# Sumo_sensors.net
KiCad netlist of a schematic drawn in EAGLE
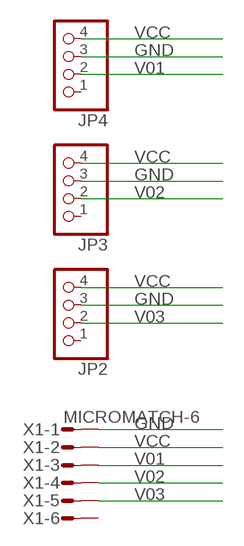
[diagram p0: schematic, sheet 1]

(export (version "E")
  (design (tool "Eeschema 10.0.6"))
  (components
    (comp (ref "JP2")
      (value "PINHD-1X4")
      (footprint "eagle-import:1X04")
      (libsource (lib "eagle-import") (part "PINHD-1X4"))
    )
    (comp (ref "JP3")
      (value "PINHD-1X4")
      (footprint "eagle-import:1X04")
      (libsource (lib "eagle-import") (part "PINHD-1X4"))
    )
    (comp (ref "JP4")
      (value "PINHD-1X4")
      (footprint "eagle-import:1X04")
      (libsource (lib "eagle-import") (part "PINHD-1X4"))
    )
    (comp (ref "X1")
      (value "MICROMATCH-6")
      (footprint "eagle-import:MICROMATCH-6")
      (fields (field (name "MPN") "7-215464-6"))
      (libsource (lib "eagle-import") (part "MICROMATCH-6"))
    )
  )
  (nets
    (net (code "1") (name "/GND") (class "Default")
      (node (ref "JP2") (pin "3") (pinfunction "3_3") (pintype "passive"))
      (node (ref "JP3") (pin "3") (pinfunction "3_3") (pintype "passive"))
      (node (ref "JP4") (pin "3") (pinfunction "3_3") (pintype "passive"))
      (node (ref "X1") (pin "1") (pinfunction "S_1") (pintype "passive"))
    )
    (net (code "2") (name "/V01") (class "Default")
      (node (ref "JP4") (pin "2") (pinfunction "2_2") (pintype "passive"))
      (node (ref "X1") (pin "3") (pinfunction "S_3") (pintype "passive"))
    )
    (net (code "3") (name "/V02") (class "Default")
      (node (ref "JP3") (pin "2") (pinfunction "2_2") (pintype "passive"))
      (node (ref "X1") (pin "4") (pinfunction "S_4") (pintype "passive"))
    )
    (net (code "4") (name "/V03") (class "Default")
      (node (ref "JP2") (pin "2") (pinfunction "2_2") (pintype "passive"))
      (node (ref "X1") (pin "5") (pinfunction "S_5") (pintype "passive"))
    )
    (net (code "5") (name "/VCC") (class "Default")
      (node (ref "JP2") (pin "4") (pinfunction "4_4") (pintype "passive"))
      (node (ref "JP3") (pin "4") (pinfunction "4_4") (pintype "passive"))
      (node (ref "JP4") (pin "4") (pinfunction "4_4") (pintype "passive"))
      (node (ref "X1") (pin "2") (pinfunction "S_2") (pintype "passive"))
    )
    (net (code "6") (name "unconnected-(JP2-Pad1)") (class "Default")
      (node (ref "JP2") (pin "1") (pinfunction "1_1") (pintype "passive"))
    )
    (net (code "7") (name "unconnected-(JP3-Pad1)") (class "Default")
      (node (ref "JP3") (pin "1") (pinfunction "1_1") (pintype "passive"))
    )
    (net (code "8") (name "unconnected-(JP4-Pad1)") (class "Default")
      (node (ref "JP4") (pin "1") (pinfunction "1_1") (pintype "passive"))
    )
    (net (code "9") (name "unconnected-(X1F-S-Pad6)") (class "Default")
      (node (ref "X1") (pin "6") (pinfunction "S_6") (pintype "passive"))
    )
  )
)
